# PoE_Si3404.net
KiCad netlist of a schematic drawn in Altium Designer
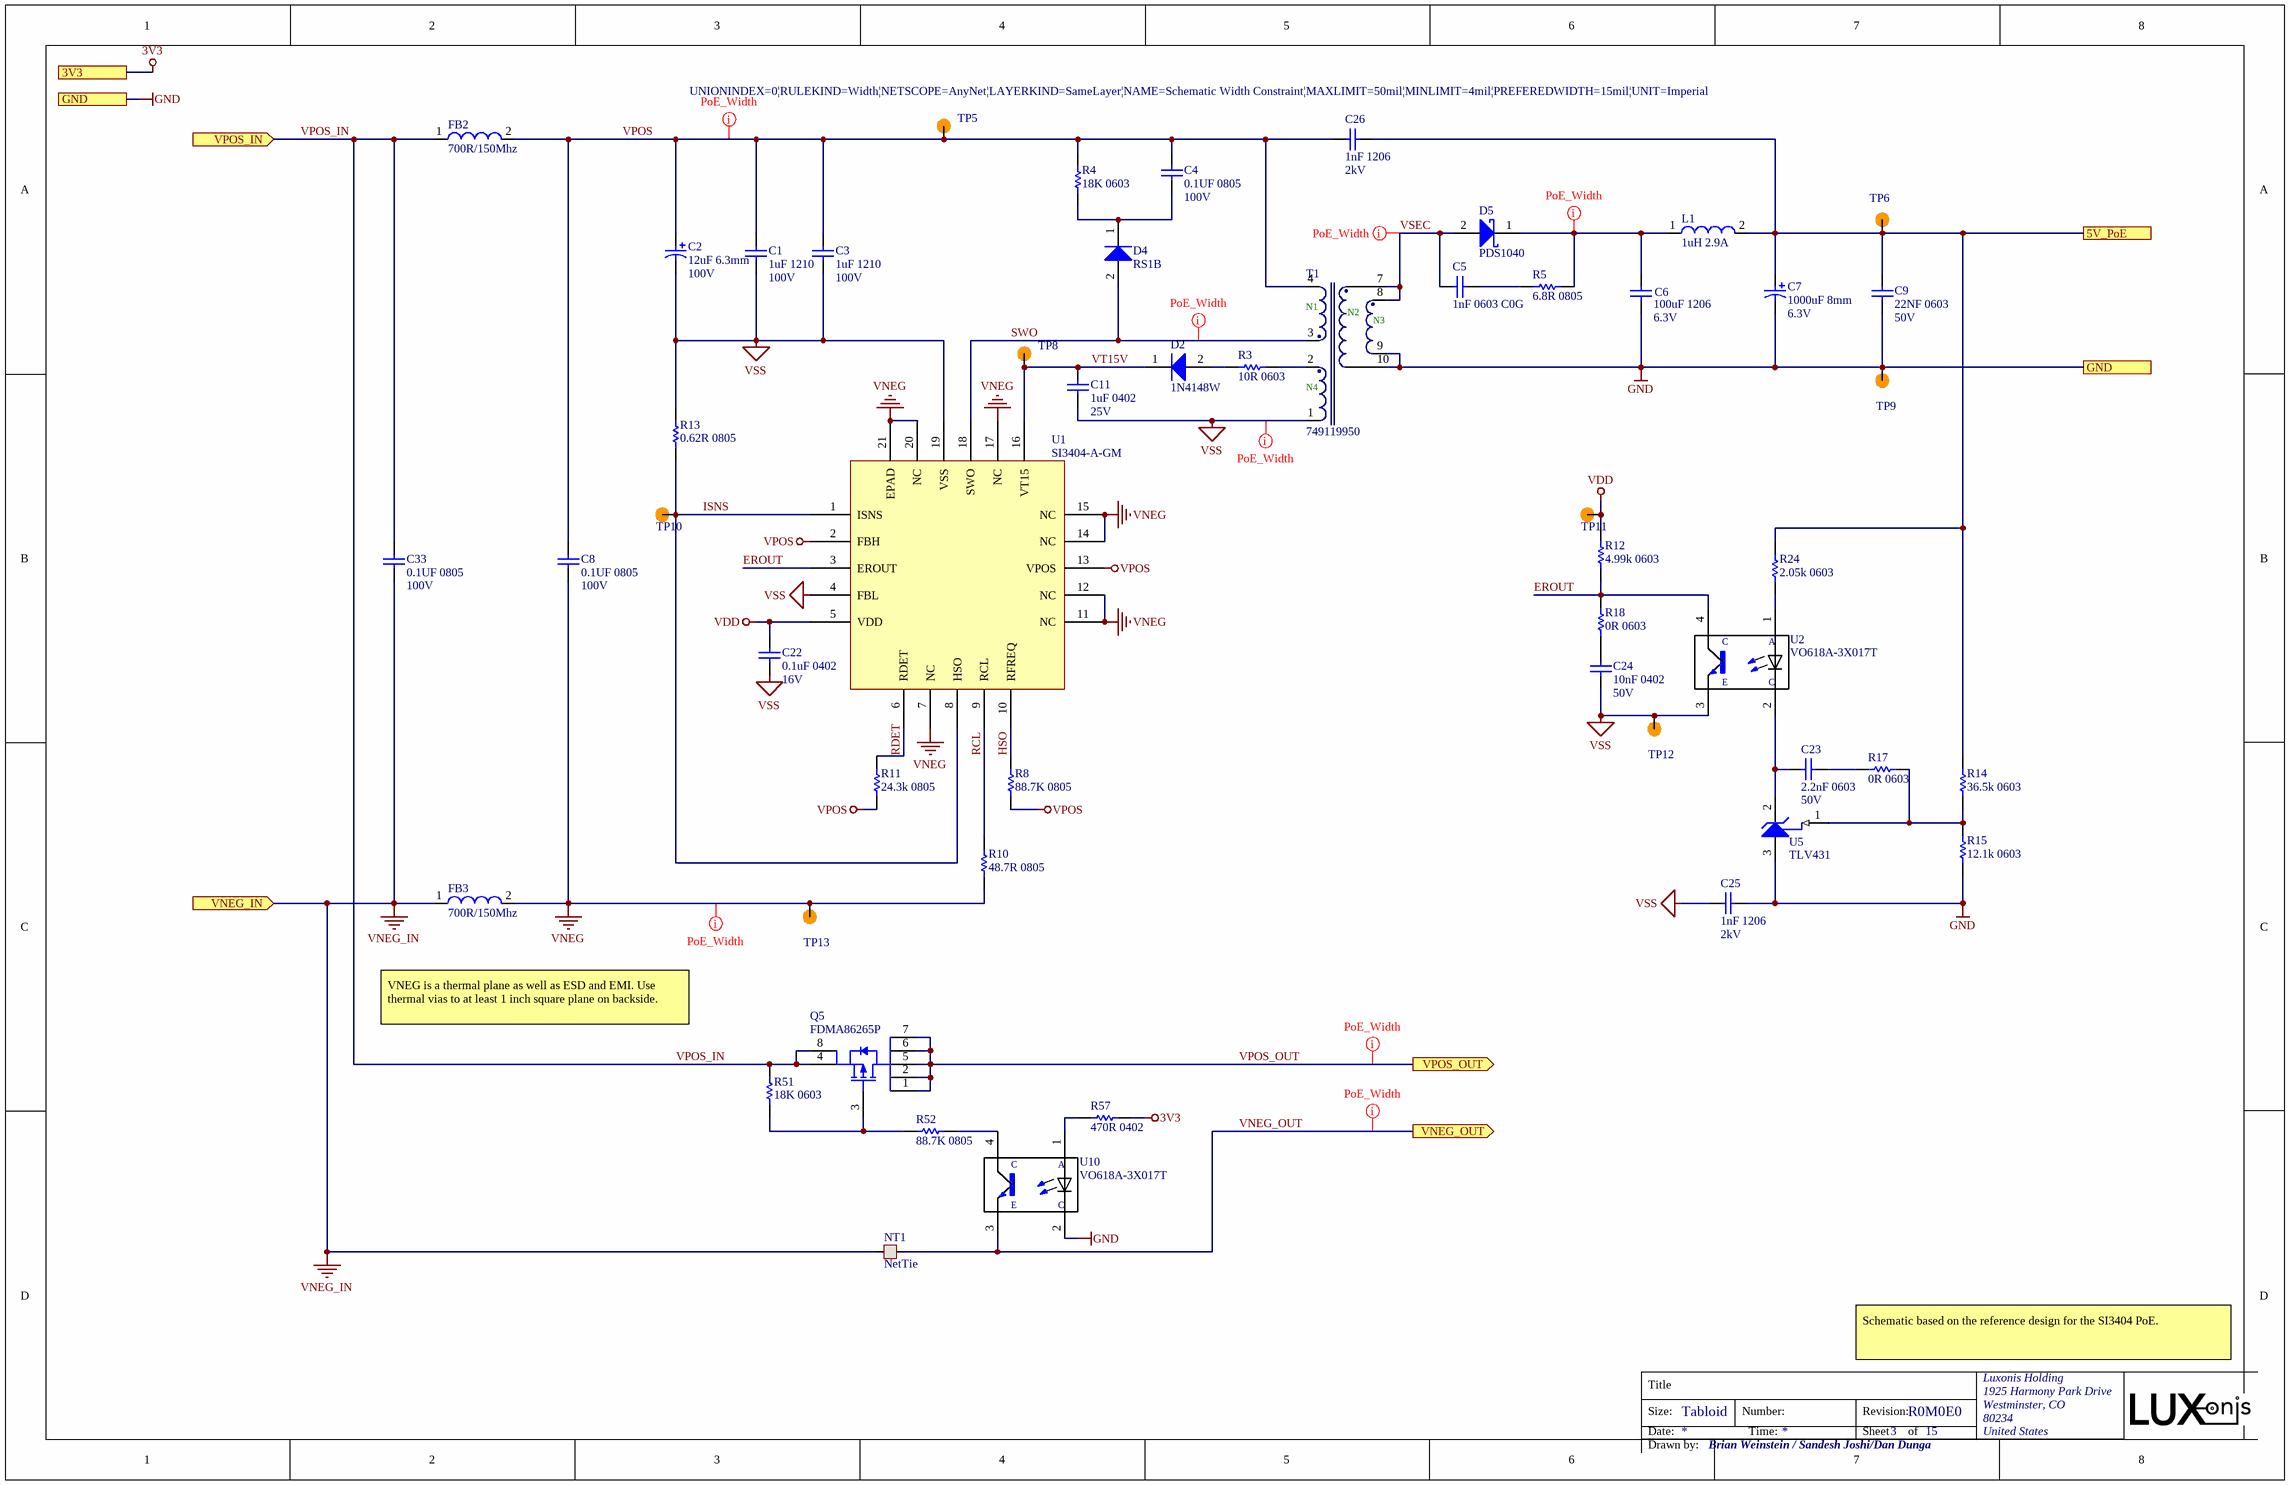
[diagram p0: PoE_Si3404.SchDoc]

(export (version "E")
  (design (tool "Eeschema 10.0.6"))
  (components
    (comp (ref "C1")
      (value "1uF 1210")
      (footprint "CAP_Altium_Vault_Generic:CAPC1210(3225)280_N")
      (description "CAP CER 1UF 100V X7R 1210")
      (fields (field (name "TOLERANCE") "10%") (field (name "VOLTAGE RATING") "100V"))
      (libsource (lib "PCBProject") (part "CL32B105KCJNNNE"))
    )
    (comp (ref "C2")
      (value "12uF 6.3mm")
      (footprint "BW2098POE:EEU-FC2A120")
      (description "CAP ALUM 12UF 20% 100V RADIAL")
      (fields (field (name "TOLERANCE") "20%") (field (name "VOLTAGE") "100V"))
      (libsource (lib "BW2098POE") (part "EEU-FC2A120"))
    )
    (comp (ref "C3")
      (value "1uF 1210")
      (footprint "CAP_Altium_Vault_Generic:CAPC1210(3225)280_N")
      (description "CAP CER 1UF 100V X7R 1210")
      (fields (field (name "TOLERANCE") "10%") (field (name "VOLTAGE RATING") "100V"))
      (libsource (lib "PCBProject") (part "CL32B105KCJNNNE"))
    )
    (comp (ref "C4")
      (value "0.1UF 0805")
      (footprint "CAP_Altium_Vault_Generic:CAPC0805(2012)145_N")
      (description "CAP CER 0.1UF 100V X7R 0805")
      (fields (field (name "TOLERANCE") "10%") (field (name "VOLTAGE RATING") "100V"))
      (libsource (lib "BW2098POE") (part "CL21B104KCFNNNE"))
    )
    (comp (ref "C5")
      (value "1nF 0603 C0G")
      (footprint "CAP_Altium_Vault_Generic:CAPC0603(1608)100_N")
      (description "CAP CER 1000PF 50V C0G/NP0 0603")
      (fields
        (field (name "MANUFACTURER") "Murata")
        (field (name "MANUFACTURER PART NUMBER") "GRM1885C1H102FA01D")
      )
      (libsource (lib "LuxonisMaster") (part "GRM1885C1H102FA01D"))
    )
    (comp (ref "C6")
      (value "100uF 1206")
      (footprint "CAP_Altium_Vault_Generic:CAPC1206(3216)190_N")
      (description "CAP CER 100UF 6.3V X5R 1206")
      (fields (field (name "TOLERANCE") "20%") (field (name "VOLTAGE") "6.3V"))
      (libsource (lib "PCBProject") (part "CL31A107MQHNNNE"))
    )
    (comp (ref "C7")
      (value "1000uF 8mm")
      (footprint "BW2098POE:ECA-0JM102")
      (description "CAP ALUM 1000UF 20% 6.3V RADIAL")
      (fields (field (name "TOLERANCE") "20%") (field (name "VOLTAGE") "6.3V"))
      (libsource (lib "BW2098POE") (part "ECA-0JM102"))
    )
    (comp (ref "C8")
      (value "0.1UF 0805")
      (footprint "CAP_Altium_Vault_Generic:CAPC0805(2012)145_N")
      (description "CAP CER 0.1UF 100V X7R 0805")
      (fields (field (name "TOLERANCE") "10%") (field (name "VOLTAGE RATING") "100V"))
      (libsource (lib "PCBProject") (part "CL21B104KCFNNNE"))
    )
    (comp (ref "C9")
      (value "22NF 0603")
      (footprint "CAP_Altium_Vault_Generic:CAPC0603(1608)100_N")
      (description "CAP CER 0.022UF 50V X7R 0603")
      (fields (field (name "TOLERANCE") "10%") (field (name "VOLTAGE") "50V"))
      (libsource (lib "LuxonisMaster") (part "C0603C223K5RACTU"))
    )
    (comp (ref "C11")
      (value "1uF 0402")
      (footprint "CAP_Altium_Vault_Generic:CAPC0402(1005)70_N")
      (description "CAP CER 1UF 25V X5R 0402 10%")
      (fields
        (field (name "TOLERANCE") "10%")
        (field (name "VOLTAGE") "25V")
        (field (name "VOLTAGE RATING") "25V")
      )
      (libsource (lib "LuxonisMaster") (part "GRM155R61E105KA12D"))
    )
    (comp (ref "C22")
      (value "0.1uF 0402")
      (footprint "CAP_Altium_Vault_Generic:CAPC0402(1005)60_N")
      (description "CAP CER 0.1UF 16V X7R 0402")
      (fields (field (name "TOLERANCE") "10%") (field (name "VOLTAGE RATING") "16V"))
      (libsource (lib "PCBProject") (part "CL05B104KO5NFNC"))
    )
    (comp (ref "C23")
      (value "2.2nF 0603")
      (footprint "CAP_Altium_Vault_Generic:CAPC0603(1608)100_N")
      (description "CAP CER 2200PF 50V C0G/NP0 0603")
      (fields (field (name "TOLERANCE") "5%") (field (name "VOLTAGE") "50V"))
      (libsource (lib "BW2098POE") (part "GRM1885C1H222JA01D"))
    )
    (comp (ref "C24")
      (value "10nF 0402")
      (footprint "CAP_Altium_Vault_Generic:CAPC0402(1005)60_N")
      (description "CAP CER 10000PF 50V X7R 0402")
      (fields
        (field (name "TOLERANCE") "10%")
        (field (name "VOLTAGE") "25V")
        (field (name "VOLTAGE RATING") "50V")
      )
      (libsource (lib "LuxonisMaster") (part "GRM155R71H103KA88D"))
    )
    (comp (ref "C25")
      (value "1nF 1206")
      (footprint "CAP_Altium_Vault_Generic:CAPC1206(3216)190_N")
      (description "CAP CER 1000PF 2KV X7R 1206")
      (fields (field (name "TOLERANCE") "10%") (field (name "VOLTAGE RATING (DC)") "2kV"))
      (libsource (lib "PCBProject") (part "C1206C102KGRACTU"))
    )
    (comp (ref "C26")
      (value "1nF 1206")
      (footprint "CAP_Altium_Vault_Generic:CAPC1206(3216)190_N")
      (description "CAP CER 1000PF 2KV X7R 1206")
      (fields (field (name "TOLERANCE") "10%") (field (name "VOLTAGE RATING (DC)") "2kV"))
      (libsource (lib "PCBProject") (part "C1206C102KGRACTU"))
    )
    (comp (ref "C33")
      (value "0.1UF 0805")
      (footprint "CAP_Altium_Vault_Generic:CAPC0805(2012)145_N")
      (description "CAP CER 0.1UF 100V X7R 0805")
      (fields (field (name "TOLERANCE") "10%") (field (name "VOLTAGE RATING") "100V"))
      (libsource (lib "PCBProject") (part "CL21B104KCFNNNE"))
    )
    (comp (ref "D2")
      (value "1N4148W")
      (footprint "BW2098POE:1N4148W-7-F")
      (description "DIODE GEN PURP 100V 300MA SOD123")
      (fields (field (name "VOLTAGE") "100V"))
      (libsource (lib "PCBProject") (part "1N4148W-7-F"))
    )
    (comp (ref "D4")
      (value "RS1B")
      (footprint "BW2098POE:RS1B")
      (description "DIODE GEN PURP 100V 1A SMA")
      (libsource (lib "BW2098POE") (part "RS1B"))
    )
    (comp (ref "D5")
      (value "PDS1040")
      (footprint "BW2098POE:PDS1040-13")
      (description "DIODE SCHOTTKY 40V 10A POWERDI5")
      (libsource (lib "PCBProject") (part "PDS1040-13"))
    )
    (comp (ref "FB2")
      (value "700R/150Mhz")
      (footprint "BW2098POE:742792040")
      (description "FERRITE BEAD 600 OHM 0805 1LN")
      (fields (field (name "TOLERANCE") "25%"))
      (libsource (lib "BW2098POE") (part "742792040"))
    )
    (comp (ref "FB3")
      (value "700R/150Mhz")
      (footprint "BW2098POE:742792040")
      (description "FERRITE BEAD 600 OHM 0805 1LN")
      (fields (field (name "TOLERANCE") "25%"))
      (libsource (lib "BW2098POE") (part "742792040"))
    )
    (comp (ref "L1")
      (value "1uH 2.9A")
      (footprint "BW2098POE:DO1608C-102MLx")
      (description "IND POWER WIREWOUND 1uH 20% 100KHz FERRITE 2.7A")
      (fields (field (name "TOLERANCE") "20%"))
      (libsource (lib "PCBProject") (part "DO1608C-102ML"))
    )
    (comp (ref "NT1")
      (value "NetTie")
      (footprint "NET_TIE_TOP_1mm")
      (description "Net tie Top/Bottom layer")
      (libsource (lib "BW2098POE_Anfa") (part "Net_Tie"))
    )
    (comp (ref "Q5")
      (value "FDMA86265P")
      (footprint "MICROFET-6")
      (description "ON SEMICONDUCTOR - FDMA86265P - MOSFET-Transistor, p-Kanal, -1 A, -150 V, 0.86 ohm, -10 V, -3.2 V")
      (libsource (lib "BW2098POE_Anfa") (part "FDMA86265P"))
    )
    (comp (ref "R3")
      (value "10R 0603")
      (footprint "RESC0603(1608)_N")
      (description "RES SMD 10 OHM 1% 1/10W 0603")
      (fields (field (name "TOLERANCE") "1%"))
      (libsource (lib "PCBProject") (part "CRCW060310R0FKEA"))
    )
    (comp (ref "R4")
      (value "18K 0603")
      (footprint "RESC0603(1608)_N")
      (description "RES SMD 18K OHM 5% 1/10W 0603")
      (fields (field (name "TOLERANCE") "5%"))
      (libsource (lib "BW2098POE") (part "RC0603JR-0718KL"))
    )
    (comp (ref "R5")
      (value "6.8R 0805")
      (footprint "RES_Altium_Vault_Generic:RESC0805(2012)_N")
      (description "RES SMD 6.8 OHM 1% 1/8W 0805")
      (fields (field (name "TOLERANCE") "1%"))
      (libsource (lib "BW2098POE") (part "RC0805FR-076R8L"))
    )
    (comp (ref "R8")
      (value "88.7K 0805")
      (footprint "RES_Altium_Vault_Generic:RESC0805(2012)_N")
      (description "RES SMD 88.7K OHM 1% 1/8W 0805")
      (fields (field (name "TOLERANCE") "1%"))
      (libsource (lib "BW2098POE") (part "CRCW080588K7FKEA"))
    )
    (comp (ref "R10")
      (value "48.7R 0805")
      (footprint "RES_Altium_Vault_Generic:RESC0805(2012)_N")
      (description "RES SMD 48.7 OHM 1% 1/8W 0805")
      (fields (field (name "TOLERANCE") "1%"))
      (libsource (lib "PCBProject") (part "RC0805FR-0748R7L"))
    )
    (comp (ref "R11")
      (value "24.3k 0805")
      (footprint "RES_Altium_Vault_Generic:RESC0805(2012)_N")
      (description "RES SMD 24.3K OHM 1% 1/8W 0805")
      (fields (field (name "TOLERANCE") "1%"))
      (libsource (lib "PCBProject") (part "CRCW080524K3FKEA"))
    )
    (comp (ref "R12")
      (value "4.99k 0603")
      (footprint "RESC0603(1608)_N")
      (description "RES SMD 4.99K OHM 1% 1/10W 0603")
      (fields (field (name "TOLERANCE") "1%"))
      (libsource (lib "PCBProject") (part "RC0603FR-074K99L"))
    )
    (comp (ref "R13")
      (value "0.62R 0805")
      (footprint "RES_Altium_Vault_Generic:RESC0805(2012)_N")
      (description "RES SMD 620 MOHM 1% 1/8W 0805")
      (fields (field (name "TOLERANCE") "1%"))
      (libsource (lib "BW2098POE") (part "RL0805FR-070R62L"))
    )
    (comp (ref "R14")
      (value "36.5k 0603")
      (footprint "RESC0603(1608)_N")
      (description "RES SMD 36.5K OHM 1% 1/10W 0603")
      (fields (field (name "TOLERANCE") "1%"))
      (libsource (lib "PCBProject") (part "RC0603FR-0736K5L"))
    )
    (comp (ref "R15")
      (value "12.1k 0603")
      (footprint "RESC0603(1608)_N")
      (description "RES SMD 12.1K OHM 1% 1/10W 0603")
      (fields (field (name "TOLERANCE") "1%"))
      (libsource (lib "PCBProject") (part "RC0603FR-0712K1L"))
    )
    (comp (ref "R17")
      (value "0R 0603")
      (footprint "RESC0603(1608)_N")
      (fields (field (name "TOLERANCE") "5%"))
      (libsource (lib "LuxonisMaster") (part "CRCW06030000Z0EA"))
    )
    (comp (ref "R18")
      (value "0R 0603")
      (footprint "RESC0603(1608)_N")
      (fields (field (name "TOLERANCE") "5%"))
      (libsource (lib "LuxonisMaster") (part "CRCW06030000Z0EA"))
    )
    (comp (ref "R24")
      (value "2.05k 0603")
      (footprint "RESC0603(1608)_N")
      (description "RES SMD 2.05K OHM 1% 1/10W 0603")
      (fields (field (name "TOLERANCE") "1%"))
      (libsource (lib "PCBProject") (part "RC0603FR-072K05L"))
    )
    (comp (ref "R51")
      (value "18K 0603")
      (footprint "RESC0603(1608)_N")
      (description "RES SMD 18K OHM 5% 1/10W 0603")
      (fields (field (name "TOLERANCE") "5%"))
      (libsource (lib "BW2098POE") (part "RC0603JR-0718KL"))
    )
    (comp (ref "R52")
      (value "88.7K 0805")
      (footprint "RESC0805(2012)_N")
      (description "RES SMD 88.7K OHM 1% 1/8W 0805")
      (fields (field (name "TOLERANCE") "1%"))
      (libsource (lib "BW2098POE") (part "CRCW080588K7FKEA"))
    )
    (comp (ref "R57")
      (value "470R 0402")
      (footprint "RESC0402(1005)_N")
      (description "RES SMD 470 OHM 1% 1/16W 0402")
      (fields (field (name "TOLERANCE") "1%"))
      (libsource (lib "LuxonisMaster") (part "CRCW0402470RFKED"))
    )
    (comp (ref "T1")
      (value "749119950")
      (footprint "BW2098POE:749119950")
      (description "TRANS FLYBACK POE 127UH SMD")
      (libsource (lib "BW2098POE") (part "749119950"))
    )
    (comp (ref "TP5")
      (value "TP100_200_NS")
      (footprint "TP100_200_NS")
      (libsource (lib "LuxonisMaster") (part "TEST_POINT"))
    )
    (comp (ref "TP6")
      (value "TP100_200_NS")
      (footprint "TP100_200_NS")
      (libsource (lib "LuxonisMaster") (part "TEST_POINT"))
    )
    (comp (ref "TP8")
      (value "TP100_200_NS")
      (footprint "TP100_200_NS")
      (libsource (lib "LuxonisMaster") (part "TEST_POINT"))
    )
    (comp (ref "TP9")
      (value "TP100_200_NS")
      (footprint "TP100_200_NS")
      (libsource (lib "LuxonisMaster") (part "TEST_POINT"))
    )
    (comp (ref "TP10")
      (value "TP100_200_NS")
      (footprint "TP100_200_NS")
      (libsource (lib "LuxonisMaster") (part "TEST_POINT"))
    )
    (comp (ref "TP11")
      (value "TP100_200_NS")
      (footprint "TP100_200_NS")
      (libsource (lib "LuxonisMaster") (part "TEST_POINT"))
    )
    (comp (ref "TP12")
      (value "TP100_200_NS")
      (footprint "TP100_200_NS")
      (libsource (lib "LuxonisMaster") (part "TEST_POINT"))
    )
    (comp (ref "TP13")
      (value "TP100_200_NS")
      (footprint "TP100_200_NS")
      (libsource (lib "LuxonisMaster") (part "TEST_POINT"))
    )
    (comp (ref "U1")
      (value "SI3404-A-GM")
      (footprint "BW2098POE:Si3404-A-GM")
      (description "IC POE CNTRL 1 CHANNEL 20QFN")
      (libsource (lib "BW2098POE") (part "SI3404-A-GM"))
    )
    (comp (ref "U2")
      (value "VO618A-3X017T")
      (footprint "BW2098POE:VO618A-3X017T")
      (description "OPTOISOLATOR 5.3KV TRANS 4-SMD")
      (libsource (lib "BW2098POE") (part "VO618A-3X017T"))
    )
    (comp (ref "U5")
      (value "TLV431")
      (footprint "BW2098POE:TLV431BCDBZR")
      (description "IC VREF SHUNT ADJ SOT23-3")
      (fields (field (name "TOLERANCE") "0.5%"))
      (libsource (lib "BW2098POE") (part "TLV431BCDBZR"))
    )
    (comp (ref "U10")
      (value "VO618A-3X017T")
      (footprint "VO618A-3X017T")
      (description "OPTOISOLATOR 5.3KV TRANS 4-SMD")
      (libsource (lib "BW2098POE") (part "VO618A-3X017T"))
    )
  )
  (nets
    (net (code "1") (name "/5V_PoE") (class "Default")
      (node (ref "C26") (pin "2") (pinfunction "2_2") (pintype "passive"))
      (node (ref "C7") (pin "1") (pinfunction "1_1") (pintype "passive"))
      (node (ref "C9") (pin "2") (pinfunction "2_2") (pintype "passive"))
      (node (ref "L1") (pin "2") (pinfunction "2_2") (pintype "passive"))
      (node (ref "R14") (pin "2") (pinfunction "2_2") (pintype "passive"))
      (node (ref "R24") (pin "2") (pinfunction "2_2") (pintype "passive"))
      (node (ref "TP6") (pin "1") (pintype "passive"))
    )
    (net (code "2") (name "/EROUT") (class "Default")
      (node (ref "R12") (pin "1") (pinfunction "1_1") (pintype "passive"))
      (node (ref "R18") (pin "2") (pinfunction "2_2") (pintype "passive"))
      (node (ref "U1") (pin "3") (pinfunction "EROUT_3") (pintype "passive"))
      (node (ref "U2") (pin "4") (pinfunction "CO_4") (pintype "passive"))
    )
    (net (code "3") (name "/HSO") (class "Default")
      (node (ref "R8") (pin "2") (pinfunction "2_2") (pintype "passive"))
      (node (ref "U1") (pin "10") (pinfunction "RFREQ_10") (pintype "passive"))
    )
    (net (code "4") (name "/ISNS") (class "Default")
      (node (ref "R13") (pin "1") (pinfunction "1_1") (pintype "passive"))
      (node (ref "TP10") (pin "1") (pintype "passive"))
      (node (ref "U1") (pin "1") (pinfunction "ISNS_1") (pintype "passive"))
      (node (ref "U1") (pin "8") (pinfunction "HSO_8") (pintype "passive"))
    )
    (net (code "5") (name "/RCL") (class "Default")
      (node (ref "R10") (pin "2") (pinfunction "2_2") (pintype "passive"))
      (node (ref "U1") (pin "9") (pinfunction "RCL_9") (pintype "passive"))
    )
    (net (code "6") (name "/RDET") (class "Default")
      (node (ref "R11") (pin "2") (pinfunction "2_2") (pintype "passive"))
      (node (ref "U1") (pin "6") (pinfunction "RDET_6") (pintype "passive"))
    )
    (net (code "7") (name "/SWO") (class "Default")
      (node (ref "D4") (pin "2") (pinfunction "A_2") (pintype "passive"))
      (node (ref "T1") (pin "3") (pinfunction "3_3") (pintype "passive"))
      (node (ref "U1") (pin "18") (pinfunction "SWO_18") (pintype "passive"))
    )
    (net (code "8") (name "/VNEG_OUT") (class "Default")
      (node (ref "NT1") (pin "2") (pinfunction "2_2") (pintype "passive"))
      (node (ref "U10") (pin "3") (pinfunction "E_3") (pintype "passive"))
    )
    (net (code "9") (name "/VPOS_IN") (class "Default")
      (node (ref "C33") (pin "2") (pinfunction "2_2") (pintype "passive"))
      (node (ref "FB2") (pin "1") (pinfunction "1_1") (pintype "passive"))
      (node (ref "Q5") (pin "4") (pinfunction "S_4") (pintype "passive"))
      (node (ref "Q5") (pin "8") (pinfunction "S_8") (pintype "passive"))
      (node (ref "R51") (pin "1") (pinfunction "1_1") (pintype "passive"))
    )
    (net (code "10") (name "/VPOS_OUT") (class "Default")
      (node (ref "Q5") (pin "1") (pinfunction "D_1") (pintype "passive"))
      (node (ref "Q5") (pin "2") (pinfunction "D_2") (pintype "passive"))
      (node (ref "Q5") (pin "5") (pinfunction "D_5") (pintype "passive"))
      (node (ref "Q5") (pin "6") (pinfunction "D_6") (pintype "passive"))
      (node (ref "Q5") (pin "7") (pinfunction "D_7") (pintype "passive"))
    )
    (net (code "11") (name "/VSEC") (class "Default")
      (node (ref "C5") (pin "2") (pinfunction "2_2") (pintype "passive"))
      (node (ref "D5") (pin "2") (pinfunction "A_2") (pintype "passive"))
      (node (ref "T1") (pin "7") (pinfunction "7_7") (pintype "passive"))
      (node (ref "T1") (pin "8") (pinfunction "8_8") (pintype "passive"))
    )
    (net (code "12") (name "/VT15V") (class "Default")
      (node (ref "C11") (pin "2") (pinfunction "2_2") (pintype "passive"))
      (node (ref "D2") (pin "1") (pinfunction "K_1") (pintype "passive"))
      (node (ref "TP8") (pin "1") (pintype "passive"))
      (node (ref "U1") (pin "16") (pinfunction "VT15_16") (pintype "passive"))
    )
    (net (code "13") (name "3V3") (class "Default")
      (node (ref "R57") (pin "2") (pinfunction "2_2") (pintype "passive"))
    )
    (net (code "14") (name "GND") (class "Default")
      (node (ref "C25") (pin "2") (pinfunction "2_2") (pintype "passive"))
      (node (ref "C6") (pin "1") (pinfunction "1_1") (pintype "passive"))
      (node (ref "C7") (pin "2") (pinfunction "2_2") (pintype "passive"))
      (node (ref "C9") (pin "1") (pinfunction "1_1") (pintype "passive"))
      (node (ref "R15") (pin "1") (pinfunction "1_1") (pintype "passive"))
      (node (ref "T1") (pin "10") (pinfunction "10_10") (pintype "passive"))
      (node (ref "T1") (pin "9") (pinfunction "9_9") (pintype "passive"))
      (node (ref "TP9") (pin "1") (pintype "passive"))
      (node (ref "U10") (pin "2") (pinfunction "C_2") (pintype "passive"))
      (node (ref "U5") (pin "3") (pinfunction "ANODE_3") (pintype "passive"))
    )
    (net (code "15") (name "Net-(C5-Pad1)") (class "Default")
      (node (ref "C5") (pin "1") (pinfunction "1_1") (pintype "passive"))
      (node (ref "R5") (pin "1") (pinfunction "1_1") (pintype "passive"))
    )
    (net (code "16") (name "Net-(C23-Pad2)") (class "Default")
      (node (ref "C23") (pin "2") (pinfunction "2_2") (pintype "passive"))
      (node (ref "R17") (pin "2") (pinfunction "2_2") (pintype "passive"))
    )
    (net (code "17") (name "Net-(C24-Pad2)") (class "Default")
      (node (ref "C24") (pin "2") (pinfunction "2_2") (pintype "passive"))
      (node (ref "R18") (pin "1") (pinfunction "1_1") (pintype "passive"))
    )
    (net (code "18") (name "Net-(D2-A)") (class "Default")
      (node (ref "D2") (pin "2") (pinfunction "A_2") (pintype "passive"))
      (node (ref "R3") (pin "1") (pinfunction "1_1") (pintype "passive"))
    )
    (net (code "19") (name "Net-(D4-K)") (class "Default")
      (node (ref "C4") (pin "1") (pinfunction "1_1") (pintype "passive"))
      (node (ref "D4") (pin "1") (pinfunction "K_1") (pintype "passive"))
      (node (ref "R4") (pin "1") (pinfunction "1_1") (pintype "passive"))
    )
    (net (code "20") (name "Net-(D5-K)") (class "Default")
      (node (ref "C6") (pin "2") (pinfunction "2_2") (pintype "passive"))
      (node (ref "D5") (pin "1") (pinfunction "K_1") (pintype "passive"))
      (node (ref "L1") (pin "1") (pinfunction "1_1") (pintype "passive"))
      (node (ref "R5") (pin "2") (pinfunction "2_2") (pintype "passive"))
    )
    (net (code "21") (name "Net-(Q5-G)") (class "Default")
      (node (ref "Q5") (pin "3") (pinfunction "G_3") (pintype "passive"))
      (node (ref "R51") (pin "2") (pinfunction "2_2") (pintype "passive"))
      (node (ref "R52") (pin "2") (pinfunction "2_2") (pintype "passive"))
    )
    (net (code "22") (name "Net-(R3-Pad2)") (class "Default")
      (node (ref "R3") (pin "2") (pinfunction "2_2") (pintype "passive"))
      (node (ref "T1") (pin "2") (pinfunction "2_2") (pintype "passive"))
    )
    (net (code "23") (name "Net-(U2-A)") (class "Default")
      (node (ref "R24") (pin "1") (pinfunction "1_1") (pintype "passive"))
      (node (ref "U2") (pin "1") (pinfunction "A_1") (pintype "passive"))
    )
    (net (code "24") (name "Net-(U2-C)") (class "Default")
      (node (ref "C23") (pin "1") (pinfunction "1_1") (pintype "passive"))
      (node (ref "U2") (pin "2") (pinfunction "C_2") (pintype "passive"))
      (node (ref "U5") (pin "2") (pinfunction "CATHODE_2") (pintype "passive"))
    )
    (net (code "25") (name "Net-(U5-REF)") (class "Default")
      (node (ref "R14") (pin "1") (pinfunction "1_1") (pintype "passive"))
      (node (ref "R15") (pin "2") (pinfunction "2_2") (pintype "passive"))
      (node (ref "R17") (pin "1") (pinfunction "1_1") (pintype "passive"))
      (node (ref "U5") (pin "1") (pinfunction "REF_1") (pintype "input"))
    )
    (net (code "26") (name "Net-(U10-A)") (class "Default")
      (node (ref "R57") (pin "1") (pinfunction "1_1") (pintype "passive"))
      (node (ref "U10") (pin "1") (pinfunction "A_1") (pintype "passive"))
    )
    (net (code "27") (name "Net-(U10-CO)") (class "Default")
      (node (ref "R52") (pin "1") (pinfunction "1_1") (pintype "passive"))
      (node (ref "U10") (pin "4") (pinfunction "CO_4") (pintype "passive"))
    )
    (net (code "28") (name "VDD") (class "Default")
      (node (ref "C22") (pin "2") (pinfunction "2_2") (pintype "passive"))
      (node (ref "R12") (pin "2") (pinfunction "2_2") (pintype "passive"))
      (node (ref "TP11") (pin "1") (pintype "passive"))
      (node (ref "U1") (pin "5") (pinfunction "VDD_5") (pintype "passive"))
    )
    (net (code "29") (name "VNEG") (class "Default")
      (node (ref "C8") (pin "1") (pinfunction "1_1") (pintype "passive"))
      (node (ref "FB3") (pin "2") (pinfunction "2_2") (pintype "passive"))
      (node (ref "R10") (pin "1") (pinfunction "1_1") (pintype "passive"))
      (node (ref "TP13") (pin "1") (pintype "passive"))
      (node (ref "U1") (pin "11") (pinfunction "NC_11") (pintype "passive"))
      (node (ref "U1") (pin "12") (pinfunction "NC_12") (pintype "passive"))
      (node (ref "U1") (pin "14") (pinfunction "NC_14") (pintype "passive"))
      (node (ref "U1") (pin "15") (pinfunction "NC_15") (pintype "passive"))
      (node (ref "U1") (pin "17") (pinfunction "NC_17") (pintype "passive"))
      (node (ref "U1") (pin "20") (pinfunction "NC_20") (pintype "passive"))
      (node (ref "U1") (pin "21") (pinfunction "EPAD_21") (pintype "passive"))
      (node (ref "U1") (pin "7") (pinfunction "NC_7") (pintype "passive"))
    )
    (net (code "30") (name "VNEG_IN") (class "Default")
      (node (ref "C33") (pin "1") (pinfunction "1_1") (pintype "passive"))
      (node (ref "FB3") (pin "1") (pinfunction "1_1") (pintype "passive"))
      (node (ref "NT1") (pin "1") (pinfunction "1_1") (pintype "passive"))
    )
    (net (code "31") (name "VPOS") (class "Default")
      (node (ref "C1") (pin "2") (pinfunction "2_2") (pintype "passive"))
      (node (ref "C2") (pin "1") (pinfunction "1_1") (pintype "passive"))
      (node (ref "C26") (pin "1") (pinfunction "1_1") (pintype "passive"))
      (node (ref "C3") (pin "2") (pinfunction "2_2") (pintype "passive"))
      (node (ref "C4") (pin "2") (pinfunction "2_2") (pintype "passive"))
      (node (ref "C8") (pin "2") (pinfunction "2_2") (pintype "passive"))
      (node (ref "FB2") (pin "2") (pinfunction "2_2") (pintype "passive"))
      (node (ref "R11") (pin "1") (pinfunction "1_1") (pintype "passive"))
      (node (ref "R4") (pin "2") (pinfunction "2_2") (pintype "passive"))
      (node (ref "R8") (pin "1") (pinfunction "1_1") (pintype "passive"))
      (node (ref "T1") (pin "4") (pinfunction "4_4") (pintype "passive"))
      (node (ref "TP5") (pin "1") (pintype "passive"))
      (node (ref "U1") (pin "13") (pinfunction "VPOS_13") (pintype "passive"))
      (node (ref "U1") (pin "2") (pinfunction "FBH_2") (pintype "passive"))
    )
    (net (code "32") (name "VSS") (class "Default")
      (node (ref "C1") (pin "1") (pinfunction "1_1") (pintype "passive"))
      (node (ref "C11") (pin "1") (pinfunction "1_1") (pintype "passive"))
      (node (ref "C2") (pin "2") (pinfunction "2_2") (pintype "passive"))
      (node (ref "C22") (pin "1") (pinfunction "1_1") (pintype "passive"))
      (node (ref "C24") (pin "1") (pinfunction "1_1") (pintype "passive"))
      (node (ref "C25") (pin "1") (pinfunction "1_1") (pintype "passive"))
      (node (ref "C3") (pin "1") (pinfunction "1_1") (pintype "passive"))
      (node (ref "R13") (pin "2") (pinfunction "2_2") (pintype "passive"))
      (node (ref "T1") (pin "1") (pinfunction "1_1") (pintype "passive"))
      (node (ref "TP12") (pin "1") (pintype "passive"))
      (node (ref "U1") (pin "19") (pinfunction "VSS_19") (pintype "passive"))
      (node (ref "U1") (pin "4") (pinfunction "FBL_4") (pintype "passive"))
      (node (ref "U2") (pin "3") (pinfunction "E_3") (pintype "passive"))
    )
  )
)
